# Signals.net
KiCad netlist of a schematic drawn in Altium Designer
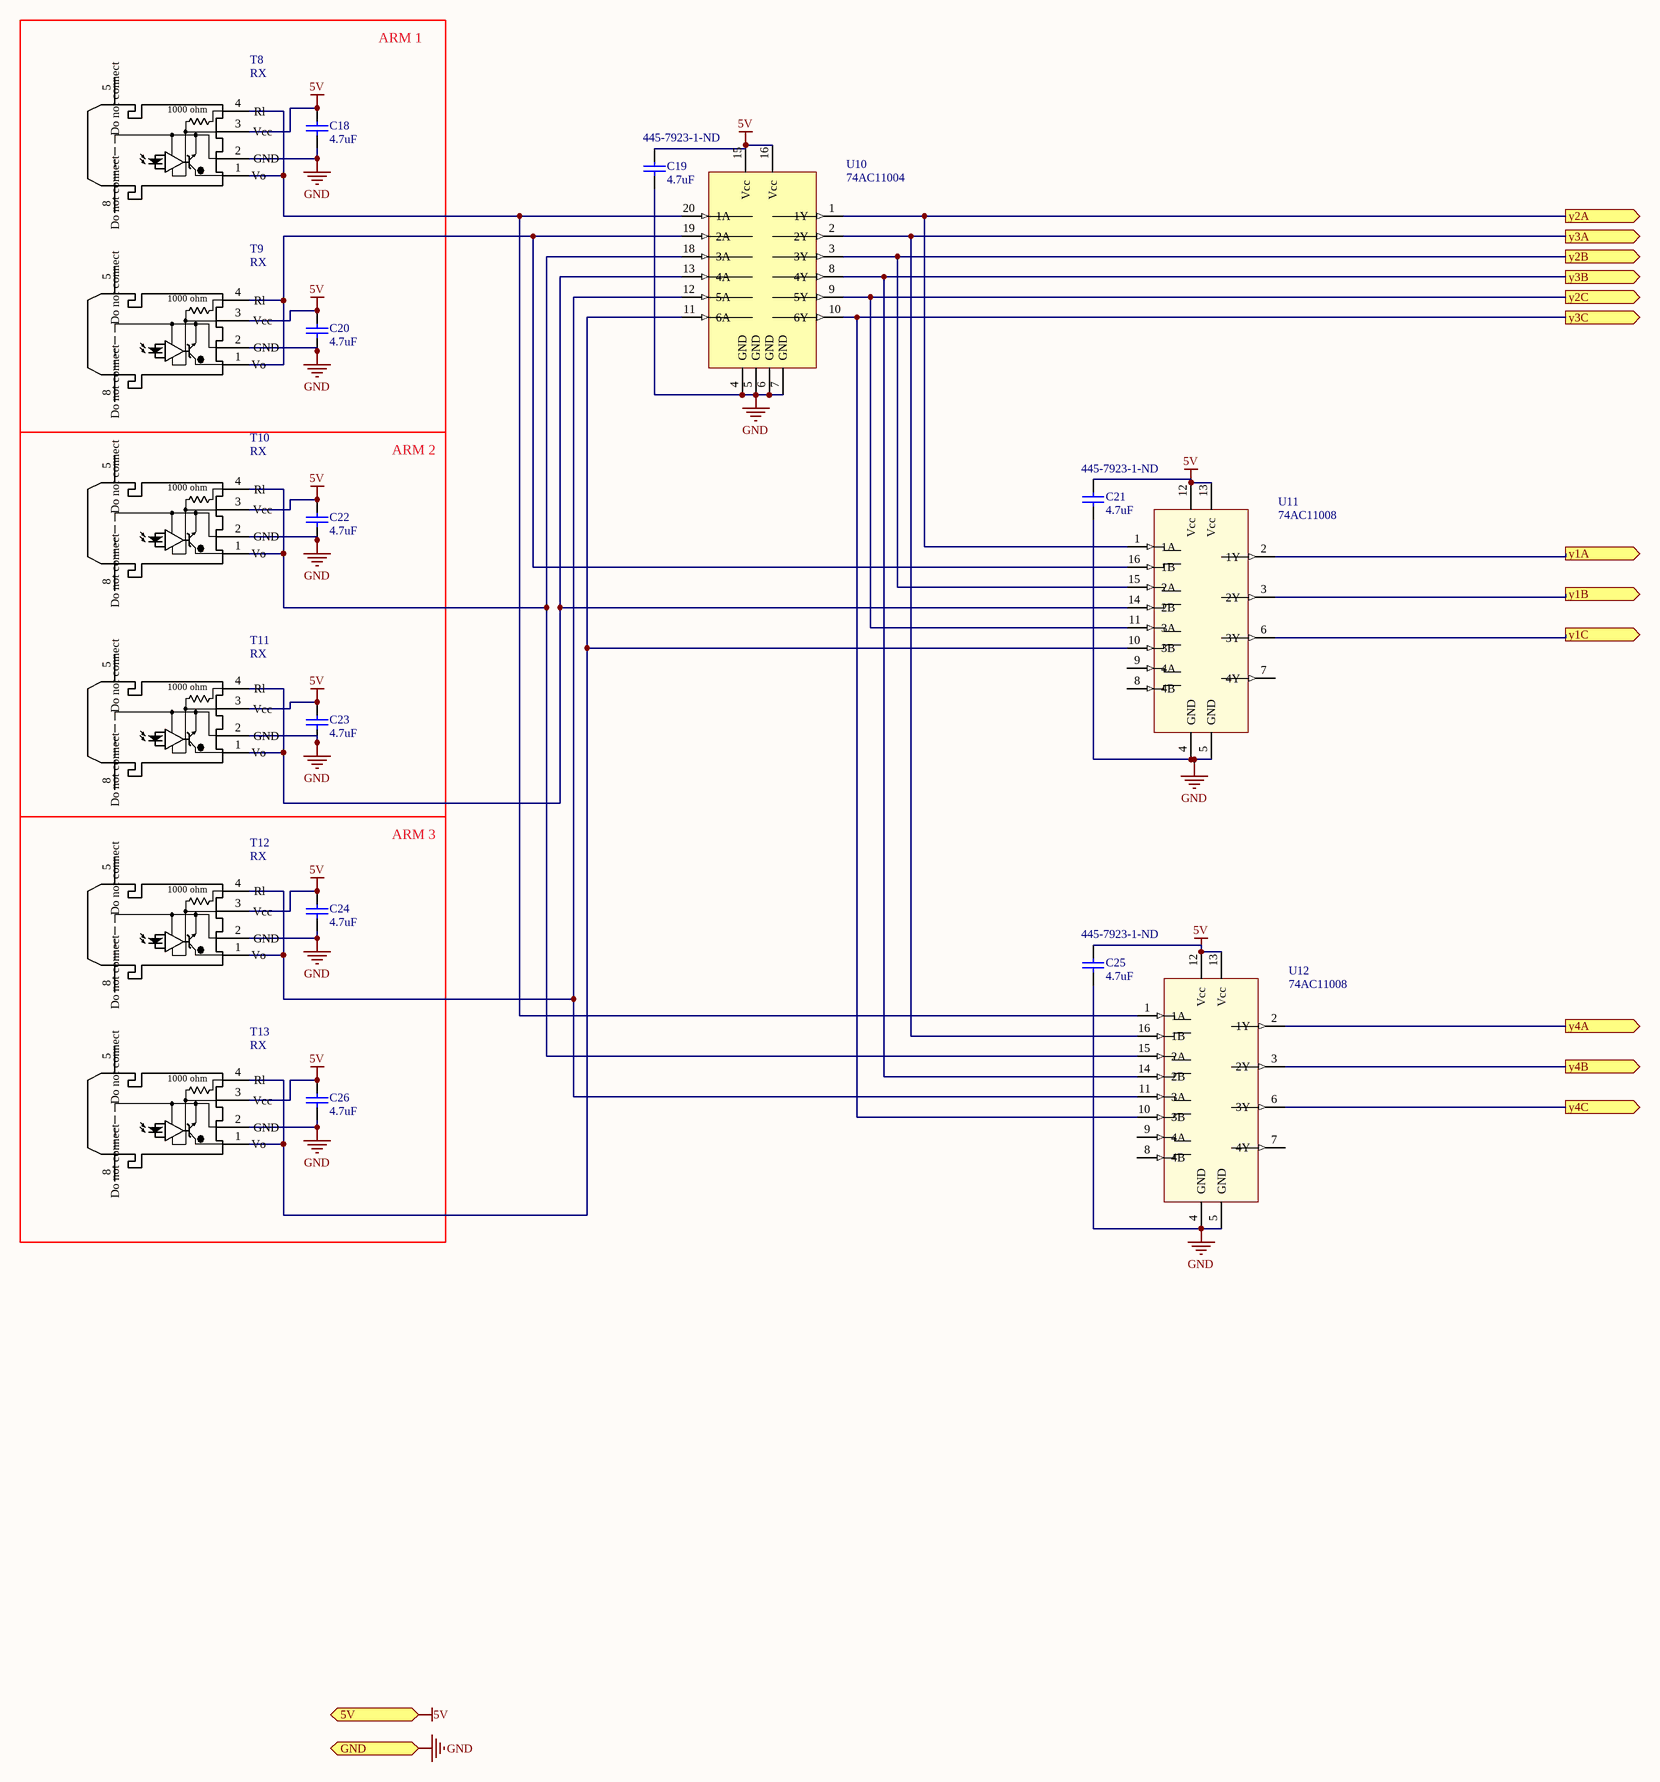
[diagram p0: Signals.SchDoc]

(export (version "E")
  (design (tool "Eeschema 10.0.6"))
  (components
    (comp (ref "C18")
      (value "4.7uF")
      (footprint "C4532")
      (description "Capacitor")
      (fields (field (name "Comment") "Cap") (field (name "PUBLISHER") "Altium Limited"))
      (libsource (lib "T-Type Converter") (part "Cap"))
    )
    (comp (ref "C19")
      (value "4.7uF")
      (footprint "C4532")
      (description "Capacitor")
      (fields
        (field (name "SUPPLIER PART NUMBER 1") "445-7923-1-ND")
        (field (name "MANUFACTURER") "TDK")
        (field (name "MANUFACTURER PART NUMBER") "CGA8N3X7S2A475K230KB")
        (field (name "PUBLISHER") "Altium Limited")
      )
      (libsource (lib "T-Type Converter") (part "Cap"))
    )
    (comp (ref "C20")
      (value "4.7uF")
      (footprint "C4532")
      (description "Capacitor")
      (fields (field (name "Comment") "Cap") (field (name "PUBLISHER") "Altium Limited"))
      (libsource (lib "T-Type Converter") (part "Cap"))
    )
    (comp (ref "C21")
      (value "4.7uF")
      (footprint "C4532")
      (description "Capacitor")
      (fields
        (field (name "SUPPLIER PART NUMBER 1") "445-7923-1-ND")
        (field (name "MANUFACTURER") "TDK")
        (field (name "MANUFACTURER PART NUMBER") "CGA8N3X7S2A475K230KB")
        (field (name "PUBLISHER") "Altium Limited")
      )
      (libsource (lib "T-Type Converter") (part "Cap"))
    )
    (comp (ref "C22")
      (value "4.7uF")
      (footprint "C4532")
      (description "Capacitor")
      (fields (field (name "Comment") "Cap") (field (name "PUBLISHER") "Altium Limited"))
      (libsource (lib "T-Type Converter") (part "Cap"))
    )
    (comp (ref "C23")
      (value "4.7uF")
      (footprint "C4532")
      (description "Capacitor")
      (fields (field (name "Comment") "Cap") (field (name "PUBLISHER") "Altium Limited"))
      (libsource (lib "T-Type Converter") (part "Cap"))
    )
    (comp (ref "C24")
      (value "4.7uF")
      (footprint "C4532")
      (description "Capacitor")
      (fields (field (name "Comment") "Cap") (field (name "PUBLISHER") "Altium Limited"))
      (libsource (lib "T-Type Converter") (part "Cap"))
    )
    (comp (ref "C25")
      (value "4.7uF")
      (footprint "C4532")
      (description "Capacitor")
      (fields
        (field (name "SUPPLIER PART NUMBER 1") "445-7923-1-ND")
        (field (name "MANUFACTURER") "TDK")
        (field (name "MANUFACTURER PART NUMBER") "CGA8N3X7S2A475K230KB")
        (field (name "PUBLISHER") "Altium Limited")
      )
      (libsource (lib "T-Type Converter") (part "Cap"))
    )
    (comp (ref "C26")
      (value "4.7uF")
      (footprint "C4532")
      (description "Capacitor")
      (fields (field (name "Comment") "Cap") (field (name "PUBLISHER") "Altium Limited"))
      (libsource (lib "T-Type Converter") (part "Cap"))
    )
    (comp (ref "T8")
      (value "RX")
      (footprint "Optics")
      (description "Optical Reciever")
      (libsource (lib "T-Type Converter") (part "HFBR-2524Z"))
    )
    (comp (ref "T9")
      (value "RX")
      (footprint "Optics")
      (description "Optical Reciever")
      (libsource (lib "T-Type Converter") (part "HFBR-2524Z"))
    )
    (comp (ref "T10")
      (value "RX")
      (footprint "Optics")
      (description "Optical Reciever")
      (libsource (lib "T-Type Converter") (part "HFBR-2524Z"))
    )
    (comp (ref "T11")
      (value "RX")
      (footprint "Optics")
      (description "Optical Reciever")
      (libsource (lib "T-Type Converter") (part "HFBR-2524Z"))
    )
    (comp (ref "T12")
      (value "RX")
      (footprint "Optics")
      (description "Optical Reciever")
      (libsource (lib "T-Type Converter") (part "HFBR-2524Z"))
    )
    (comp (ref "T13")
      (value "RX")
      (footprint "Optics")
      (description "Optical Reciever")
      (libsource (lib "T-Type Converter") (part "HFBR-2524Z"))
    )
    (comp (ref "U10")
      (value "74AC11004")
      (footprint "R-PDIP-T20")
      (description "Hex Inverter")
      (fields
        (field (name "MANUFACTURER") "Texas Instruments")
        (field (name "MANUFACTURER PART NUMBER") "74AC11004N")
      )
      (libsource (lib "T-Type Converter") (part "74AC11004"))
    )
    (comp (ref "U11")
      (value "74AC11008")
      (footprint "R-PDIP-T16")
      (description "AND GATE")
      (fields
        (field (name "MANUFACTURER") "Texas Instruments")
        (field (name "MANUFACTURER PART NUMBER") "74AC11008N")
      )
      (libsource (lib "T-Type Converter") (part "74AC11008"))
    )
    (comp (ref "U12")
      (value "74AC11008")
      (footprint "R-PDIP-T16")
      (description "AND GATE")
      (fields
        (field (name "MANUFACTURER") "Texas Instruments")
        (field (name "MANUFACTURER PART NUMBER") "74AC11008N")
      )
      (libsource (lib "T-Type Converter") (part "74AC11008"))
    )
  )
  (nets
    (net (code "1") (name "/y1A") (class "Default")
      (node (ref "U11") (pin "2") (pinfunction "1Y_2") (pintype "output"))
    )
    (net (code "2") (name "/y1B") (class "Default")
      (node (ref "U11") (pin "3") (pinfunction "2Y_3") (pintype "output"))
    )
    (net (code "3") (name "/y1C") (class "Default")
      (node (ref "U11") (pin "6") (pinfunction "3Y_6") (pintype "output"))
    )
    (net (code "4") (name "/y2A") (class "Default")
      (node (ref "U10") (pin "1") (pinfunction "1Y_1") (pintype "output"))
      (node (ref "U11") (pin "1") (pinfunction "1A_1") (pintype "input"))
    )
    (net (code "5") (name "/y2B") (class "Default")
      (node (ref "U10") (pin "3") (pinfunction "3Y_3") (pintype "output"))
      (node (ref "U11") (pin "15") (pinfunction "2A_15") (pintype "input"))
    )
    (net (code "6") (name "/y2C") (class "Default")
      (node (ref "U10") (pin "9") (pinfunction "5Y_9") (pintype "output"))
      (node (ref "U11") (pin "11") (pinfunction "3A_11") (pintype "input"))
    )
    (net (code "7") (name "/y3A") (class "Default")
      (node (ref "U10") (pin "2") (pinfunction "2Y_2") (pintype "output"))
      (node (ref "U12") (pin "16") (pinfunction "1B_16") (pintype "input"))
    )
    (net (code "8") (name "/y3B") (class "Default")
      (node (ref "U10") (pin "8") (pinfunction "4Y_8") (pintype "output"))
      (node (ref "U12") (pin "14") (pinfunction "2B_14") (pintype "input"))
    )
    (net (code "9") (name "/y3C") (class "Default")
      (node (ref "U10") (pin "10") (pinfunction "6Y_10") (pintype "output"))
      (node (ref "U12") (pin "10") (pinfunction "3B_10") (pintype "input"))
    )
    (net (code "10") (name "/y4A") (class "Default")
      (node (ref "U12") (pin "2") (pinfunction "1Y_2") (pintype "output"))
    )
    (net (code "11") (name "/y4B") (class "Default")
      (node (ref "U12") (pin "3") (pinfunction "2Y_3") (pintype "output"))
    )
    (net (code "12") (name "/y4C") (class "Default")
      (node (ref "U12") (pin "6") (pinfunction "3Y_6") (pintype "output"))
    )
    (net (code "13") (name "5V") (class "Default")
      (node (ref "C18") (pin "2") (pinfunction "2_2") (pintype "passive"))
      (node (ref "C19") (pin "2") (pinfunction "2_2") (pintype "passive"))
      (node (ref "C20") (pin "2") (pinfunction "2_2") (pintype "passive"))
      (node (ref "C21") (pin "2") (pinfunction "2_2") (pintype "passive"))
      (node (ref "C22") (pin "2") (pinfunction "2_2") (pintype "passive"))
      (node (ref "C23") (pin "2") (pinfunction "2_2") (pintype "passive"))
      (node (ref "C24") (pin "2") (pinfunction "2_2") (pintype "passive"))
      (node (ref "C25") (pin "2") (pinfunction "2_2") (pintype "passive"))
      (node (ref "C26") (pin "2") (pinfunction "2_2") (pintype "passive"))
      (node (ref "T10") (pin "3") (pinfunction "Vcc_3") (pintype "passive"))
      (node (ref "T11") (pin "3") (pinfunction "Vcc_3") (pintype "passive"))
      (node (ref "T12") (pin "3") (pinfunction "Vcc_3") (pintype "passive"))
      (node (ref "T13") (pin "3") (pinfunction "Vcc_3") (pintype "passive"))
      (node (ref "T8") (pin "3") (pinfunction "Vcc_3") (pintype "passive"))
      (node (ref "T9") (pin "3") (pinfunction "Vcc_3") (pintype "passive"))
      (node (ref "U10") (pin "15") (pinfunction "Vcc_15") (pintype "power_in"))
      (node (ref "U10") (pin "16") (pinfunction "Vcc_16") (pintype "power_in"))
      (node (ref "U11") (pin "12") (pinfunction "Vcc_12") (pintype "power_in"))
      (node (ref "U11") (pin "13") (pinfunction "Vcc_13") (pintype "power_in"))
      (node (ref "U12") (pin "12") (pinfunction "Vcc_12") (pintype "power_in"))
      (node (ref "U12") (pin "13") (pinfunction "Vcc_13") (pintype "power_in"))
    )
    (net (code "14") (name "GND") (class "Default")
      (node (ref "C18") (pin "1") (pinfunction "1_1") (pintype "passive"))
      (node (ref "C19") (pin "1") (pinfunction "1_1") (pintype "passive"))
      (node (ref "C20") (pin "1") (pinfunction "1_1") (pintype "passive"))
      (node (ref "C21") (pin "1") (pinfunction "1_1") (pintype "passive"))
      (node (ref "C22") (pin "1") (pinfunction "1_1") (pintype "passive"))
      (node (ref "C23") (pin "1") (pinfunction "1_1") (pintype "passive"))
      (node (ref "C24") (pin "1") (pinfunction "1_1") (pintype "passive"))
      (node (ref "C25") (pin "1") (pinfunction "1_1") (pintype "passive"))
      (node (ref "C26") (pin "1") (pinfunction "1_1") (pintype "passive"))
      (node (ref "T10") (pin "2") (pinfunction "GND_2") (pintype "passive"))
      (node (ref "T11") (pin "2") (pinfunction "GND_2") (pintype "passive"))
      (node (ref "T12") (pin "2") (pinfunction "GND_2") (pintype "passive"))
      (node (ref "T13") (pin "2") (pinfunction "GND_2") (pintype "passive"))
      (node (ref "T8") (pin "2") (pinfunction "GND_2") (pintype "passive"))
      (node (ref "T9") (pin "2") (pinfunction "GND_2") (pintype "passive"))
      (node (ref "U10") (pin "4") (pinfunction "GND_4") (pintype "passive"))
      (node (ref "U10") (pin "5") (pinfunction "GND_5") (pintype "passive"))
      (node (ref "U10") (pin "6") (pinfunction "GND_6") (pintype "passive"))
      (node (ref "U10") (pin "7") (pinfunction "GND_7") (pintype "passive"))
      (node (ref "U11") (pin "4") (pinfunction "GND_4") (pintype "passive"))
      (node (ref "U11") (pin "5") (pinfunction "GND_5") (pintype "passive"))
      (node (ref "U12") (pin "4") (pinfunction "GND_4") (pintype "passive"))
      (node (ref "U12") (pin "5") (pinfunction "GND_5") (pintype "passive"))
    )
    (net (code "15") (name "Net-(T8-Rl)") (class "Default")
      (node (ref "T8") (pin "1") (pinfunction "Vo_1") (pintype "passive"))
      (node (ref "T8") (pin "4") (pinfunction "Rl_4") (pintype "passive"))
      (node (ref "U10") (pin "20") (pinfunction "1A_20") (pintype "input"))
      (node (ref "U12") (pin "1") (pinfunction "1A_1") (pintype "input"))
    )
    (net (code "16") (name "Net-(T9-Rl)") (class "Default")
      (node (ref "T9") (pin "1") (pinfunction "Vo_1") (pintype "passive"))
      (node (ref "T9") (pin "4") (pinfunction "Rl_4") (pintype "passive"))
      (node (ref "U10") (pin "19") (pinfunction "2A_19") (pintype "input"))
      (node (ref "U11") (pin "16") (pinfunction "1B_16") (pintype "input"))
    )
    (net (code "17") (name "Net-(T10-Rl)") (class "Default")
      (node (ref "T10") (pin "1") (pinfunction "Vo_1") (pintype "passive"))
      (node (ref "T10") (pin "4") (pinfunction "Rl_4") (pintype "passive"))
      (node (ref "U10") (pin "18") (pinfunction "3A_18") (pintype "input"))
      (node (ref "U12") (pin "15") (pinfunction "2A_15") (pintype "input"))
    )
    (net (code "18") (name "Net-(T11-Rl)") (class "Default")
      (node (ref "T11") (pin "1") (pinfunction "Vo_1") (pintype "passive"))
      (node (ref "T11") (pin "4") (pinfunction "Rl_4") (pintype "passive"))
      (node (ref "U10") (pin "13") (pinfunction "4A_13") (pintype "input"))
      (node (ref "U11") (pin "14") (pinfunction "2B_14") (pintype "input"))
    )
    (net (code "19") (name "Net-(T12-Rl)") (class "Default")
      (node (ref "T12") (pin "1") (pinfunction "Vo_1") (pintype "passive"))
      (node (ref "T12") (pin "4") (pinfunction "Rl_4") (pintype "passive"))
      (node (ref "U10") (pin "12") (pinfunction "5A_12") (pintype "input"))
      (node (ref "U12") (pin "11") (pinfunction "3A_11") (pintype "input"))
    )
    (net (code "20") (name "Net-(T13-Rl)") (class "Default")
      (node (ref "T13") (pin "1") (pinfunction "Vo_1") (pintype "passive"))
      (node (ref "T13") (pin "4") (pinfunction "Rl_4") (pintype "passive"))
      (node (ref "U10") (pin "11") (pinfunction "6A_11") (pintype "input"))
      (node (ref "U11") (pin "10") (pinfunction "3B_10") (pintype "input"))
    )
    (net (code "21") (name "unconnected-(T8-Do_not_connect-Pad5)") (class "Default")
      (node (ref "T8") (pin "5") (pinfunction "Do_not_connect_5") (pintype "passive"))
    )
    (net (code "22") (name "unconnected-(T8-Do_not_connect-Pad8)") (class "Default")
      (node (ref "T8") (pin "8") (pinfunction "Do_not_connect_8") (pintype "passive"))
    )
    (net (code "23") (name "unconnected-(T9-Do_not_connect-Pad5)") (class "Default")
      (node (ref "T9") (pin "5") (pinfunction "Do_not_connect_5") (pintype "passive"))
    )
    (net (code "24") (name "unconnected-(T9-Do_not_connect-Pad8)") (class "Default")
      (node (ref "T9") (pin "8") (pinfunction "Do_not_connect_8") (pintype "passive"))
    )
    (net (code "25") (name "unconnected-(T10-Do_not_connect-Pad5)") (class "Default")
      (node (ref "T10") (pin "5") (pinfunction "Do_not_connect_5") (pintype "passive"))
    )
    (net (code "26") (name "unconnected-(T10-Do_not_connect-Pad8)") (class "Default")
      (node (ref "T10") (pin "8") (pinfunction "Do_not_connect_8") (pintype "passive"))
    )
    (net (code "27") (name "unconnected-(T11-Do_not_connect-Pad5)") (class "Default")
      (node (ref "T11") (pin "5") (pinfunction "Do_not_connect_5") (pintype "passive"))
    )
    (net (code "28") (name "unconnected-(T11-Do_not_connect-Pad8)") (class "Default")
      (node (ref "T11") (pin "8") (pinfunction "Do_not_connect_8") (pintype "passive"))
    )
    (net (code "29") (name "unconnected-(T12-Do_not_connect-Pad5)") (class "Default")
      (node (ref "T12") (pin "5") (pinfunction "Do_not_connect_5") (pintype "passive"))
    )
    (net (code "30") (name "unconnected-(T12-Do_not_connect-Pad8)") (class "Default")
      (node (ref "T12") (pin "8") (pinfunction "Do_not_connect_8") (pintype "passive"))
    )
    (net (code "31") (name "unconnected-(T13-Do_not_connect-Pad5)") (class "Default")
      (node (ref "T13") (pin "5") (pinfunction "Do_not_connect_5") (pintype "passive"))
    )
    (net (code "32") (name "unconnected-(T13-Do_not_connect-Pad8)") (class "Default")
      (node (ref "T13") (pin "8") (pinfunction "Do_not_connect_8") (pintype "passive"))
    )
    (net (code "33") (name "unconnected-(U11-4A-Pad9)") (class "Default")
      (node (ref "U11") (pin "9") (pinfunction "4A_9") (pintype "input"))
    )
    (net (code "34") (name "unconnected-(U11-4B-Pad8)") (class "Default")
      (node (ref "U11") (pin "8") (pinfunction "4B_8") (pintype "input"))
    )
    (net (code "35") (name "unconnected-(U11-4Y-Pad7)") (class "Default")
      (node (ref "U11") (pin "7") (pinfunction "4Y_7") (pintype "output"))
    )
    (net (code "36") (name "unconnected-(U12-4A-Pad9)") (class "Default")
      (node (ref "U12") (pin "9") (pinfunction "4A_9") (pintype "input"))
    )
    (net (code "37") (name "unconnected-(U12-4B-Pad8)") (class "Default")
      (node (ref "U12") (pin "8") (pinfunction "4B_8") (pintype "input"))
    )
    (net (code "38") (name "unconnected-(U12-4Y-Pad7)") (class "Default")
      (node (ref "U12") (pin "7") (pinfunction "4Y_7") (pintype "output"))
    )
  )
)
